# WS100.net
KiCad netlist of a schematic drawn in Altium Designer
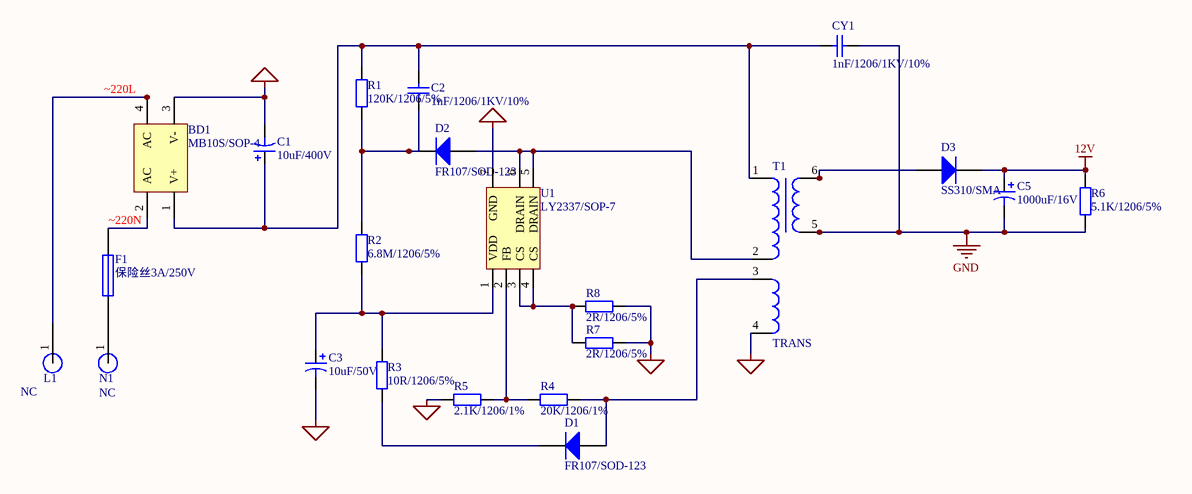
[diagram p0: WS100.SchDoc]

(export (version "E")
  (design (tool "Eeschema 10.0.6"))
  (components
    (comp (ref "BD1")
      (value "MB10S/SOP-4")
      (footprint "MBL10S")
      (description "整流桥 MB10S/SOP-4")
      (fields (field (name "PUBLISHER") "Altium Limited"))
      (libsource (lib "Miscellaneous Devices") (part "Bridge2"))
    )
    (comp (ref "C1")
      (value "10uF/400V")
      (footprint "400V/10uF 8*12mm")
      (description "直插电解电容10uF/400V")
      (fields (field (name "PUBLISHER") "Altium Limited"))
      (libsource (lib "Miscellaneous Devices") (part "Cap Pol1"))
    )
    (comp (ref "C2")
      (value "1nF/1206/1KV/10%")
      (footprint "C1206")
      (description "1nF/1206/50V/10%")
      (fields (field (name "PUBLISHER") "Altium Limited"))
      (libsource (lib "Miscellaneous Devices") (part "Cap"))
    )
    (comp (ref "C3")
      (value "10uF/50V")
      (footprint "50V/10uF")
      (description "直插电解电容10uF/50V")
      (fields (field (name "PUBLISHER") "Altium Limited"))
      (libsource (lib "Miscellaneous Devices") (part "Cap Pol1"))
    )
    (comp (ref "C5")
      (value "1000uF/16V")
      (footprint "16V/1000uF 8*16mm -2")
      (description "直插电解电容1000uF/16V")
      (fields (field (name "PUBLISHER") "Altium Limited"))
      (libsource (lib "Miscellaneous Devices") (part "Cap Pol1"))
    )
    (comp (ref "CY1")
      (value "1nF/1206/1KV/10%")
      (footprint "C1206")
      (description "1nF/1206/50V/10%")
      (fields (field (name "PUBLISHER") "Altium Limited"))
      (libsource (lib "Miscellaneous Devices") (part "Cap"))
    )
    (comp (ref "D1")
      (value "FR107/SOD-123")
      (footprint "SOD123")
      (description "快恢复二极管 FR107 封装SOD-123")
      (fields (field (name "PUBLISHER") "Altium Limited"))
      (libsource (lib "Miscellaneous Devices") (part "Diode"))
    )
    (comp (ref "D2")
      (value "FR107/SOD-123")
      (footprint "SOD123")
      (description "快恢复二极管 FR107 封装SOD-123")
      (fields (field (name "PUBLISHER") "Altium Limited"))
      (libsource (lib "Miscellaneous Devices") (part "Diode"))
    )
    (comp (ref "D3")
      (value "SS310/SMA")
      (footprint "SMA")
      (description "肖特基二极管 SS310/封装 SMA")
      (fields (field (name "PUBLISHER") "Altium Limited"))
      (libsource (lib "Miscellaneous Devices") (part "Diode"))
    )
    (comp (ref "F1")
      (value "保险丝3A/250V")
      (footprint "方块保险丝4*8mm")
      (fields (field (name "PUBLISHER") "Altium Limited"))
      (libsource (lib "Miscellaneous Devices") (part "Fuse 1"))
    )
    (comp (ref "L1")
      (value "NC")
      (footprint "PAD")
      (description "焊接点")
      (libsource (lib "TS_2A") (part "Welding-hole"))
    )
    (comp (ref "N1")
      (value "NC")
      (footprint "PAD")
      (description "焊接点")
      (libsource (lib "TS_2A") (part "Welding-hole"))
    )
    (comp (ref "R1")
      (value "120K/1206/5%")
      (footprint "R1206")
      (description "Resistor 120K/1206/5%")
      (fields (field (name "PUBLISHER") "Altium Limited"))
      (libsource (lib "Miscellaneous Devices") (part "Res2"))
    )
    (comp (ref "R2")
      (value "6.8M/1206/5%")
      (footprint "R1206")
      (description "Resistor 6.8M/1206/5%  6.8兆欧姆")
      (fields (field (name "PUBLISHER") "Altium Limited"))
      (libsource (lib "Miscellaneous Devices") (part "Res2"))
    )
    (comp (ref "R3")
      (value "10R/1206/5%")
      (footprint "R1206")
      (description "Resistor 10R/1206/5%")
      (fields (field (name "PUBLISHER") "Altium Limited"))
      (libsource (lib "") (part "Res2_2"))
    )
    (comp (ref "R4")
      (value "20K/1206/1%")
      (footprint "R1206")
      (description "Resistor 20K/1206/1%")
      (fields (field (name "PUBLISHER") "Altium Limited"))
      (libsource (lib "") (part "Res2_1"))
    )
    (comp (ref "R5")
      (value "2.1K/1206/1%")
      (footprint "R1206")
      (description "Resistor 2.1K/1206/1%")
      (fields (field (name "PUBLISHER") "Altium Limited"))
      (libsource (lib "") (part "Res2_1"))
    )
    (comp (ref "R6")
      (value "5.1K/1206/5%")
      (footprint "R1206")
      (description "Resistor 5.1K/1206/5%")
      (fields (field (name "PUBLISHER") "Altium Limited"))
      (libsource (lib "Miscellaneous Devices") (part "Res2"))
    )
    (comp (ref "R7")
      (value "2R/1206/5%")
      (footprint "R1206")
      (description "Resistor 2R/1206/5%")
      (fields (field (name "PUBLISHER") "Altium Limited"))
      (libsource (lib "") (part "Res2_1"))
    )
    (comp (ref "R8")
      (value "2R/1206/5%")
      (footprint "R1206")
      (description "Resistor 2R/1206/5%")
      (fields (field (name "PUBLISHER") "Altium Limited"))
      (libsource (lib "") (part "Res2_1"))
    )
    (comp (ref "T1")
      (value "TRANS")
      (footprint "EPC-17_2")
      (description "变压器")
      (libsource (lib "Schlib1") (part "TRANS"))
    )
    (comp (ref "U1")
      (value "LY2337/SOP-7")
      (footprint "SOP-7")
      (libsource (lib "Schlib1") (part "Component_1"))
    )
  )
  (nets
    (net (code "1") (name "/~220L") (class "Default")
      (node (ref "BD1") (pin "4") (pinfunction "AC_4") (pintype "passive"))
      (node (ref "L1") (pin "1") (pinfunction "1_1") (pintype "passive"))
    )
    (net (code "2") (name "/~220N") (class "Default")
      (node (ref "BD1") (pin "2") (pinfunction "AC_2") (pintype "passive"))
      (node (ref "F1") (pin "2") (pinfunction "2_2") (pintype "passive"))
    )
    (net (code "3") (name "12V") (class "Default")
      (node (ref "C5") (pin "1") (pinfunction "1_1") (pintype "passive"))
      (node (ref "D3") (pin "2") (pinfunction "K_2") (pintype "passive"))
      (node (ref "R6") (pin "2") (pinfunction "2_2") (pintype "passive"))
    )
    (net (code "4") (name "AGND") (class "Default")
      (node (ref "BD1") (pin "3") (pinfunction "V-_3") (pintype "passive"))
      (node (ref "C1") (pin "2") (pinfunction "2_2") (pintype "passive"))
      (node (ref "C3") (pin "2") (pinfunction "2_2") (pintype "passive"))
      (node (ref "R5") (pin "1") (pinfunction "1_1") (pintype "passive"))
      (node (ref "R7") (pin "2") (pinfunction "2_2") (pintype "passive"))
      (node (ref "R8") (pin "2") (pinfunction "2_2") (pintype "passive"))
      (node (ref "T1") (pin "4") (pinfunction "5_4") (pintype "passive"))
      (node (ref "U1") (pin "7") (pinfunction "GND_7") (pintype "passive"))
    )
    (net (code "5") (name "GND") (class "Default")
      (node (ref "C5") (pin "2") (pinfunction "2_2") (pintype "passive"))
      (node (ref "CY1") (pin "2") (pinfunction "2_2") (pintype "passive"))
      (node (ref "R6") (pin "1") (pinfunction "1_1") (pintype "passive"))
      (node (ref "T1") (pin "5") (pinfunction "5_5") (pintype "passive"))
    )
    (net (code "6") (name "Net-(BD1-V+)") (class "Default")
      (node (ref "BD1") (pin "1") (pinfunction "V+_1") (pintype "passive"))
      (node (ref "C1") (pin "1") (pinfunction "1_1") (pintype "passive"))
      (node (ref "C2") (pin "2") (pinfunction "2_2") (pintype "passive"))
      (node (ref "CY1") (pin "1") (pinfunction "1_1") (pintype "passive"))
      (node (ref "R1") (pin "2") (pinfunction "2_2") (pintype "passive"))
      (node (ref "T1") (pin "1") (pinfunction "1_1") (pintype "passive"))
    )
    (net (code "7") (name "Net-(D1-A)") (class "Default")
      (node (ref "D1") (pin "1") (pinfunction "A_1") (pintype "passive"))
      (node (ref "R4") (pin "2") (pinfunction "2_2") (pintype "passive"))
      (node (ref "T1") (pin "3") (pinfunction "3_3") (pintype "passive"))
    )
    (net (code "8") (name "Net-(D1-K)") (class "Default")
      (node (ref "D1") (pin "2") (pinfunction "K_2") (pintype "passive"))
      (node (ref "R3") (pin "2") (pinfunction "2_2") (pintype "passive"))
    )
    (net (code "9") (name "Net-(D2-A)") (class "Default")
      (node (ref "D2") (pin "1") (pinfunction "A_1") (pintype "passive"))
      (node (ref "T1") (pin "2") (pinfunction "2_2") (pintype "passive"))
      (node (ref "U1") (pin "5") (pinfunction "DRAIN_5") (pintype "passive"))
      (node (ref "U1") (pin "6") (pinfunction "DRAIN_6") (pintype "passive"))
    )
    (net (code "10") (name "Net-(D2-K)") (class "Default")
      (node (ref "C2") (pin "1") (pinfunction "1_1") (pintype "passive"))
      (node (ref "D2") (pin "2") (pinfunction "K_2") (pintype "passive"))
      (node (ref "R1") (pin "1") (pinfunction "1_1") (pintype "passive"))
      (node (ref "R2") (pin "2") (pinfunction "2_2") (pintype "passive"))
    )
    (net (code "11") (name "Net-(D3-A)") (class "Default")
      (node (ref "D3") (pin "1") (pinfunction "A_1") (pintype "passive"))
      (node (ref "T1") (pin "6") (pinfunction "6_6") (pintype "passive"))
    )
    (net (code "12") (name "Net-(F1-Pad1)") (class "Default")
      (node (ref "F1") (pin "1") (pinfunction "1_1") (pintype "passive"))
      (node (ref "N1") (pin "1") (pinfunction "1_1") (pintype "passive"))
    )
    (net (code "13") (name "Net-(R7-Pad1)") (class "Default")
      (node (ref "R7") (pin "1") (pinfunction "1_1") (pintype "passive"))
      (node (ref "R8") (pin "1") (pinfunction "1_1") (pintype "passive"))
      (node (ref "U1") (pin "3") (pinfunction "CS_3") (pintype "passive"))
      (node (ref "U1") (pin "4") (pinfunction "CS_4") (pintype "passive"))
    )
    (net (code "14") (name "Net-(U1-FB)") (class "Default")
      (node (ref "R4") (pin "1") (pinfunction "1_1") (pintype "passive"))
      (node (ref "R5") (pin "2") (pinfunction "2_2") (pintype "passive"))
      (node (ref "U1") (pin "2") (pinfunction "FB_2") (pintype "passive"))
    )
    (net (code "15") (name "Net-(U1-VDD)") (class "Default")
      (node (ref "C3") (pin "1") (pinfunction "1_1") (pintype "passive"))
      (node (ref "R2") (pin "1") (pinfunction "1_1") (pintype "passive"))
      (node (ref "R3") (pin "1") (pinfunction "1_1") (pintype "passive"))
      (node (ref "U1") (pin "1") (pinfunction "VDD_1") (pintype "passive"))
    )
  )
)
